# ai_levelshifter_MOSFET.net
KiCad netlist of a schematic drawn in EAGLE
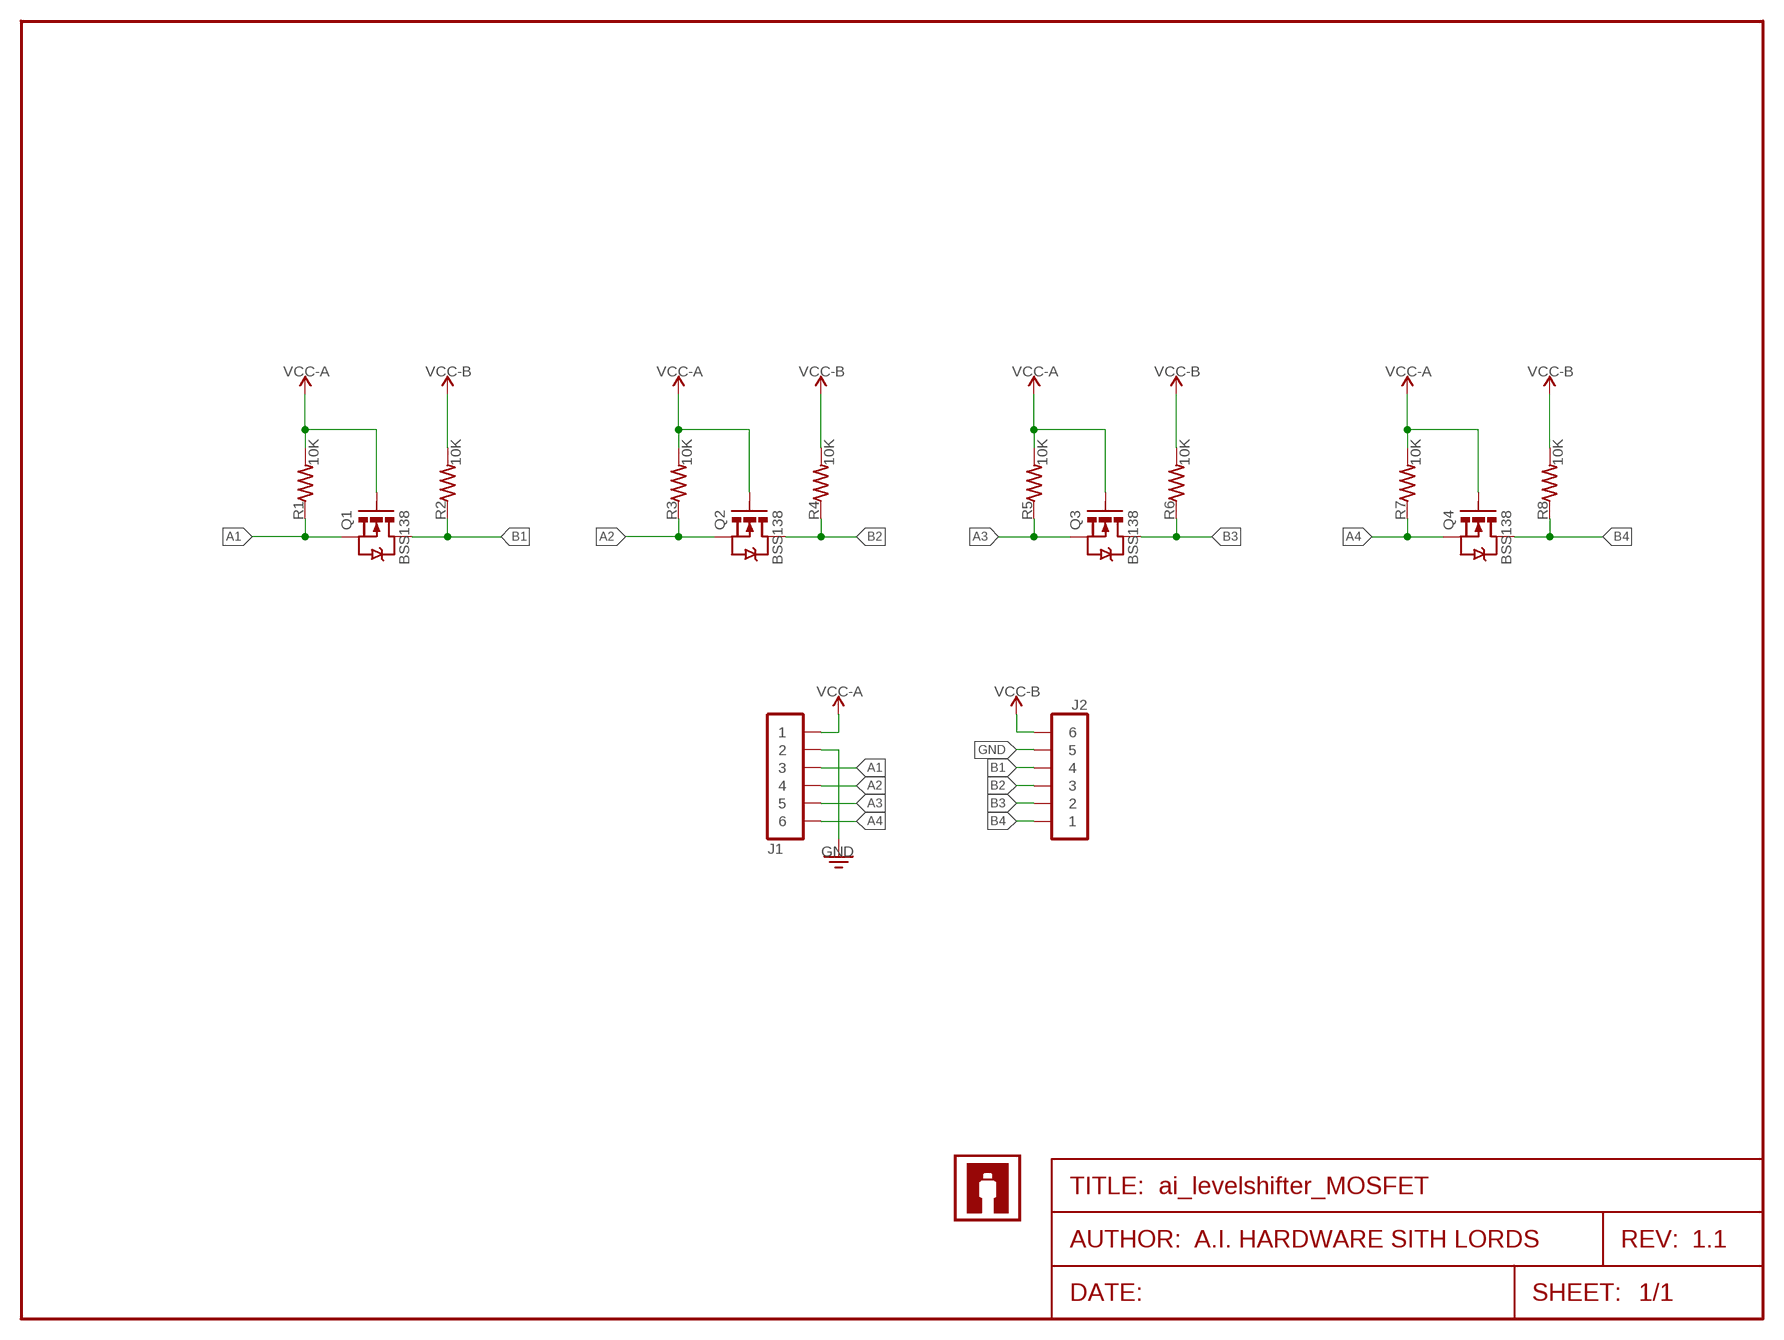
[diagram p0: schematic, sheet 1]

(export (version "E")
  (design (tool "Eeschema 10.0.6"))
  (components
    (comp (ref "J1")
      (value "1X06")
      (footprint "eagle-import:1X06")
      (libsource (lib "eagle-import") (part "1X06"))
    )
    (comp (ref "J2")
      (value "1X06NOFIRST")
      (footprint "eagle-import:1X06-NOFIRST")
      (libsource (lib "eagle-import") (part "1X06NOFIRST"))
    )
    (comp (ref "Q1")
      (value "BSS138")
      (footprint "eagle-import:SOT-23")
      (libsource (lib "eagle-import") (part "FET-NMOS-BSS138"))
    )
    (comp (ref "Q2")
      (value "BSS138")
      (footprint "eagle-import:SOT-23")
      (libsource (lib "eagle-import") (part "FET-NMOS-BSS138"))
    )
    (comp (ref "Q3")
      (value "BSS138")
      (footprint "eagle-import:SOT-23")
      (libsource (lib "eagle-import") (part "FET-NMOS-BSS138"))
    )
    (comp (ref "Q4")
      (value "BSS138")
      (footprint "eagle-import:SOT-23")
      (libsource (lib "eagle-import") (part "FET-NMOS-BSS138"))
    )
    (comp (ref "R1")
      (value "10K")
      (footprint "eagle-import:RES-0603")
      (libsource (lib "eagle-import") (part "RES0603"))
    )
    (comp (ref "R2")
      (value "10K")
      (footprint "eagle-import:RES-0603")
      (libsource (lib "eagle-import") (part "RES0603"))
    )
    (comp (ref "R3")
      (value "10K")
      (footprint "eagle-import:RES-0603")
      (libsource (lib "eagle-import") (part "RES0603"))
    )
    (comp (ref "R4")
      (value "10K")
      (footprint "eagle-import:RES-0603")
      (libsource (lib "eagle-import") (part "RES0603"))
    )
    (comp (ref "R5")
      (value "10K")
      (footprint "eagle-import:RES-0603")
      (libsource (lib "eagle-import") (part "RES0603"))
    )
    (comp (ref "R6")
      (value "10K")
      (footprint "eagle-import:RES-0603")
      (libsource (lib "eagle-import") (part "RES0603"))
    )
    (comp (ref "R7")
      (value "10K")
      (footprint "eagle-import:RES-0603")
      (libsource (lib "eagle-import") (part "RES0603"))
    )
    (comp (ref "R8")
      (value "10K")
      (footprint "eagle-import:RES-0603")
      (libsource (lib "eagle-import") (part "RES0603"))
    )
    (comp (ref "U$1")
      (value "AI-LOGOXS")
      (footprint "eagle-import:AI-LOGO-XS")
      (libsource (lib "eagle-import") (part "AI-LOGOXS"))
    )
  )
  (nets
    (net (code "1") (name "A1") (class "Default")
      (node (ref "J1") (pin "3") (pinfunction "3_3") (pintype "bidirectional"))
      (node (ref "Q1") (pin "2") (pinfunction "S_2") (pintype "passive"))
      (node (ref "R1") (pin "1") (pinfunction "1_1") (pintype "passive"))
    )
    (net (code "2") (name "A2") (class "Default")
      (node (ref "J1") (pin "4") (pinfunction "4_4") (pintype "bidirectional"))
      (node (ref "Q2") (pin "2") (pinfunction "S_2") (pintype "passive"))
      (node (ref "R3") (pin "1") (pinfunction "1_1") (pintype "passive"))
    )
    (net (code "3") (name "A3") (class "Default")
      (node (ref "J1") (pin "5") (pinfunction "5_5") (pintype "bidirectional"))
      (node (ref "Q3") (pin "2") (pinfunction "S_2") (pintype "passive"))
      (node (ref "R5") (pin "1") (pinfunction "1_1") (pintype "passive"))
    )
    (net (code "4") (name "A4") (class "Default")
      (node (ref "J1") (pin "6") (pinfunction "6_6") (pintype "bidirectional"))
      (node (ref "Q4") (pin "2") (pinfunction "S_2") (pintype "passive"))
      (node (ref "R7") (pin "1") (pinfunction "1_1") (pintype "passive"))
    )
    (net (code "5") (name "B1") (class "Default")
      (node (ref "J2") (pin "4") (pinfunction "4_4") (pintype "bidirectional"))
      (node (ref "Q1") (pin "3") (pinfunction "D_3") (pintype "passive"))
      (node (ref "R2") (pin "1") (pinfunction "1_1") (pintype "passive"))
    )
    (net (code "6") (name "B2") (class "Default")
      (node (ref "J2") (pin "3") (pinfunction "3_3") (pintype "bidirectional"))
      (node (ref "Q2") (pin "3") (pinfunction "D_3") (pintype "passive"))
      (node (ref "R4") (pin "1") (pinfunction "1_1") (pintype "passive"))
    )
    (net (code "7") (name "B3") (class "Default")
      (node (ref "J2") (pin "2") (pinfunction "2_2") (pintype "bidirectional"))
      (node (ref "Q3") (pin "3") (pinfunction "D_3") (pintype "passive"))
      (node (ref "R6") (pin "1") (pinfunction "1_1") (pintype "passive"))
    )
    (net (code "8") (name "B4") (class "Default")
      (node (ref "J2") (pin "1") (pinfunction "1_1") (pintype "bidirectional"))
      (node (ref "Q4") (pin "3") (pinfunction "D_3") (pintype "passive"))
      (node (ref "R8") (pin "1") (pinfunction "1_1") (pintype "passive"))
    )
    (net (code "9") (name "GND") (class "Default")
      (node (ref "J1") (pin "2") (pinfunction "2_2") (pintype "bidirectional"))
      (node (ref "J2") (pin "5") (pinfunction "5_5") (pintype "bidirectional"))
    )
    (net (code "10") (name "VCC-A") (class "Default")
      (node (ref "J1") (pin "1") (pinfunction "1_1") (pintype "bidirectional"))
      (node (ref "Q1") (pin "1") (pinfunction "G_1") (pintype "passive"))
      (node (ref "Q2") (pin "1") (pinfunction "G_1") (pintype "passive"))
      (node (ref "Q3") (pin "1") (pinfunction "G_1") (pintype "passive"))
      (node (ref "Q4") (pin "1") (pinfunction "G_1") (pintype "passive"))
      (node (ref "R1") (pin "2") (pinfunction "2_2") (pintype "passive"))
      (node (ref "R3") (pin "2") (pinfunction "2_2") (pintype "passive"))
      (node (ref "R5") (pin "2") (pinfunction "2_2") (pintype "passive"))
      (node (ref "R7") (pin "2") (pinfunction "2_2") (pintype "passive"))
    )
    (net (code "11") (name "VCC-B") (class "Default")
      (node (ref "J2") (pin "6") (pinfunction "6_6") (pintype "bidirectional"))
      (node (ref "R2") (pin "2") (pinfunction "2_2") (pintype "passive"))
      (node (ref "R4") (pin "2") (pinfunction "2_2") (pintype "passive"))
      (node (ref "R6") (pin "2") (pinfunction "2_2") (pintype "passive"))
      (node (ref "R8") (pin "2") (pinfunction "2_2") (pintype "passive"))
    )
  )
)
